# ES_Datalogger.net
KiCad netlist of a schematic drawn in EAGLE
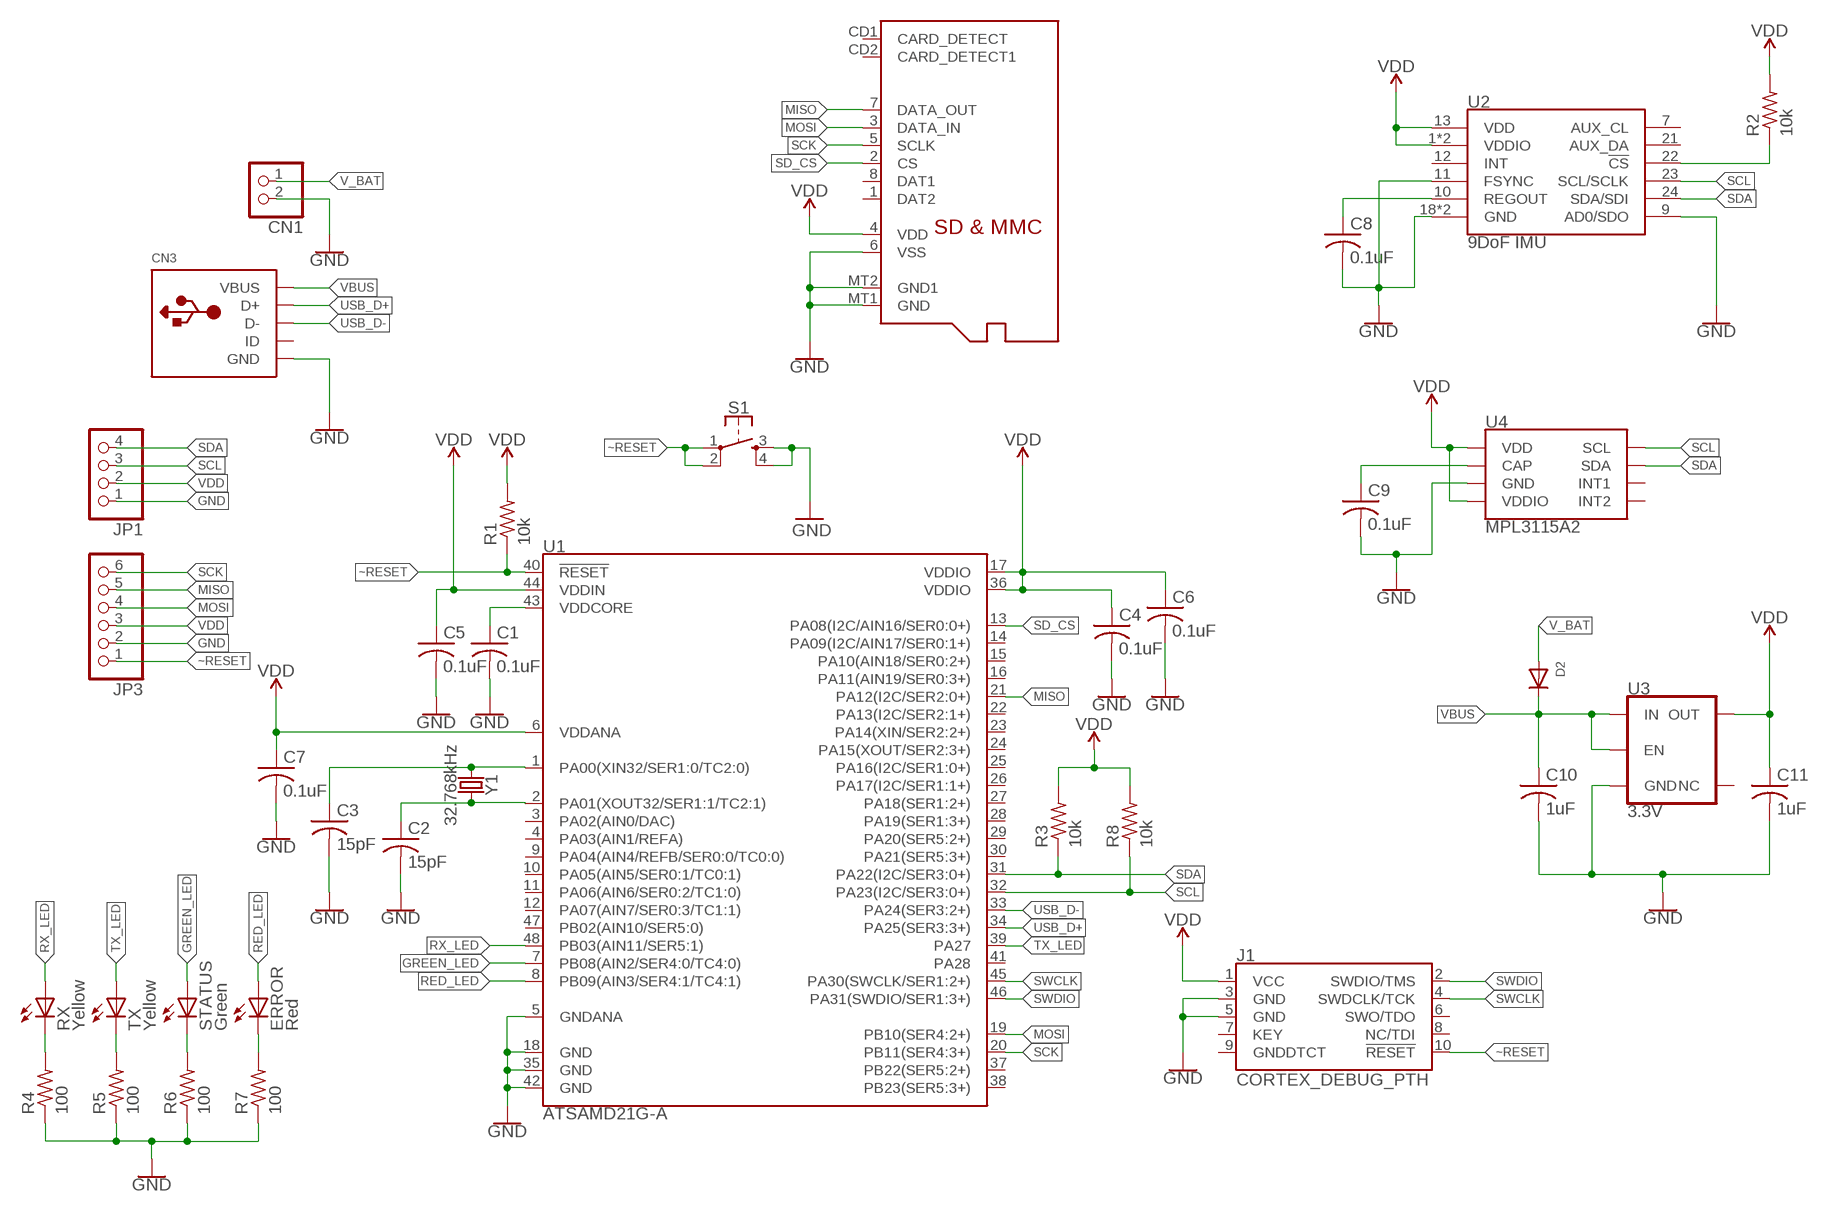
[diagram p0: schematic, sheet 1]

(export (version "E")
  (design (tool "Eeschema 10.0.6"))
  (components
    (comp (ref "C1")
      (value "0.1uF")
      (footprint "eagle-import:C0805")
      (libsource (lib "eagle-import") (part "C-USC0805"))
    )
    (comp (ref "C2")
      (value "15pF")
      (footprint "eagle-import:C0805")
      (libsource (lib "eagle-import") (part "C-USC0805"))
    )
    (comp (ref "C3")
      (value "15pF")
      (footprint "eagle-import:C0805")
      (libsource (lib "eagle-import") (part "C-USC0805"))
    )
    (comp (ref "C4")
      (value "0.1uF")
      (footprint "eagle-import:C0805")
      (libsource (lib "eagle-import") (part "C-USC0805"))
    )
    (comp (ref "C5")
      (value "0.1uF")
      (footprint "eagle-import:C0805")
      (libsource (lib "eagle-import") (part "C-USC0805"))
    )
    (comp (ref "C6")
      (value "0.1uF")
      (footprint "eagle-import:C0805")
      (libsource (lib "eagle-import") (part "C-USC0805"))
    )
    (comp (ref "C7")
      (value "0.1uF")
      (footprint "eagle-import:C0805")
      (libsource (lib "eagle-import") (part "C-USC0805"))
    )
    (comp (ref "C8")
      (value "0.1uF")
      (footprint "eagle-import:C0805")
      (libsource (lib "eagle-import") (part "C-USC0805"))
    )
    (comp (ref "C9")
      (value "0.1uF")
      (footprint "eagle-import:C0805")
      (libsource (lib "eagle-import") (part "C-USC0805"))
    )
    (comp (ref "C10")
      (value "1uF")
      (footprint "eagle-import:C0805")
      (libsource (lib "eagle-import") (part "C-USC0805"))
    )
    (comp (ref "C11")
      (value "1uF")
      (footprint "eagle-import:C0805")
      (libsource (lib "eagle-import") (part "C-USC0805"))
    )
    (comp (ref "CN1")
      (value "JST_2PIN-SMT")
      (footprint "eagle-import:JST-PH-2-SMT")
      (libsource (lib "eagle-import") (part "JST_2PIN-SMT"))
    )
    (comp (ref "CN3")
      (value "USBMOLEX")
      (footprint "eagle-import:USB-MINIB-THM-MOLEX")
      (libsource (lib "eagle-import") (part "USBMOLEX"))
    )
    (comp (ref "D2")
      (value "DIODE_SOD-123FL")
      (footprint "eagle-import:SOD-123FL")
      (libsource (lib "eagle-import") (part "DIODE_SOD-123FL"))
    )
    (comp (ref "ERROR")
      (value "Red")
      (footprint "eagle-import:CHIPLED_0805")
      (libsource (lib "eagle-import") (part "LEDCHIPLED_0805"))
    )
    (comp (ref "J1")
      (value "CORTEX_DEBUG_PTH")
      (footprint "eagle-import:2X5-PTH-1.27MM")
      (libsource (lib "eagle-import") (part "CORTEX_DEBUG_PTH"))
    )
    (comp (ref "JP1")
      (value "PINHD-1X4")
      (footprint "eagle-import:1X04")
      (libsource (lib "eagle-import") (part "PINHD-1X4"))
    )
    (comp (ref "JP3")
      (value "PINHD-1X6")
      (footprint "eagle-import:1X06")
      (libsource (lib "eagle-import") (part "PINHD-1X6"))
    )
    (comp (ref "R1")
      (value "10k")
      (footprint "eagle-import:R0805")
      (libsource (lib "eagle-import") (part "R-US_R0805"))
    )
    (comp (ref "R2")
      (value "10k")
      (footprint "eagle-import:R0805")
      (libsource (lib "eagle-import") (part "R-US_R0805"))
    )
    (comp (ref "R3")
      (value "10k")
      (footprint "eagle-import:R0805")
      (libsource (lib "eagle-import") (part "R-US_R0805"))
    )
    (comp (ref "R4")
      (value "100")
      (footprint "eagle-import:R0805")
      (libsource (lib "eagle-import") (part "R-US_R0805"))
    )
    (comp (ref "R5")
      (value "100")
      (footprint "eagle-import:R0805")
      (libsource (lib "eagle-import") (part "R-US_R0805"))
    )
    (comp (ref "R6")
      (value "100")
      (footprint "eagle-import:R0805")
      (libsource (lib "eagle-import") (part "R-US_R0805"))
    )
    (comp (ref "R7")
      (value "100")
      (footprint "eagle-import:R0805")
      (libsource (lib "eagle-import") (part "R-US_R0805"))
    )
    (comp (ref "R8")
      (value "10k")
      (footprint "eagle-import:R0805")
      (libsource (lib "eagle-import") (part "R-US_R0805"))
    )
    (comp (ref "RX")
      (value "Yellow")
      (footprint "eagle-import:CHIPLED_0805")
      (libsource (lib "eagle-import") (part "LEDCHIPLED_0805"))
    )
    (comp (ref "S1")
      (value "MOMENTARY-SWITCH-SPST-2-SMD-5.2MM")
      (footprint "eagle-import:TACTILE_SWITCH_SMD_5.2MM")
      (libsource (lib "eagle-import") (part "MOMENTARY-SWITCH-SPST-2-SMD-5.2MM"))
    )
    (comp (ref "STATUS")
      (value "Green")
      (footprint "eagle-import:CHIPLED_0805")
      (libsource (lib "eagle-import") (part "LEDCHIPLED_0805"))
    )
    (comp (ref "TX")
      (value "Yellow")
      (footprint "eagle-import:CHIPLED_0805")
      (libsource (lib "eagle-import") (part "LEDCHIPLED_0805"))
    )
    (comp (ref "U$1")
      (value "MICROSD")
      (footprint "eagle-import:MICROSD")
      (libsource (lib "eagle-import") (part "MICROSD"))
    )
    (comp (ref "U1")
      (value "ATSAMD21G-A")
      (footprint "eagle-import:TQFP-48")
      (libsource (lib "eagle-import") (part "ATSAMD21G-A"))
    )
    (comp (ref "U2")
      (value "9DoF IMU")
      (footprint "eagle-import:QFN24-3X3")
      (libsource (lib "eagle-import") (part "MPU-9250"))
    )
    (comp (ref "U3")
      (value "3.3V")
      (footprint "eagle-import:SOT23-5")
      (libsource (lib "eagle-import") (part "V_REG_AP2112K-3.3V"))
    )
    (comp (ref "U4")
      (value "MPL3115A2")
      (footprint "eagle-import:LGA-8-5X3")
      (libsource (lib "eagle-import") (part "MPL3115A2"))
    )
    (comp (ref "Y1")
      (value "32.768kHz")
      (footprint "eagle-import:CRYSTAL-SMD-MC-146")
      (libsource (lib "eagle-import") (part "CRYSTAL-32.768KHZSMD-MC146"))
    )
  )
  (nets
    (net (code "1") (name "/~{RESET}") (class "Default")
      (node (ref "J1") (pin "10") (pinfunction "~{RESET}_10") (pintype "bidirectional"))
      (node (ref "JP3") (pin "1") (pinfunction "1_1") (pintype "passive"))
      (node (ref "R1") (pin "1") (pinfunction "1_1") (pintype "passive"))
      (node (ref "S1") (pin "1") (pinfunction "1_1") (pintype "passive"))
      (node (ref "S1") (pin "2") (pinfunction "2_2") (pintype "passive"))
      (node (ref "U1") (pin "40") (pinfunction "~{RESET}_40") (pintype "bidirectional"))
    )
    (net (code "2") (name "GND") (class "Default")
      (node (ref "C1") (pin "2") (pinfunction "2_2") (pintype "passive"))
      (node (ref "C10") (pin "2") (pinfunction "2_2") (pintype "passive"))
      (node (ref "C11") (pin "2") (pinfunction "2_2") (pintype "passive"))
      (node (ref "C2") (pin "2") (pinfunction "2_2") (pintype "passive"))
      (node (ref "C3") (pin "2") (pinfunction "2_2") (pintype "passive"))
      (node (ref "C4") (pin "2") (pinfunction "2_2") (pintype "passive"))
      (node (ref "C5") (pin "2") (pinfunction "2_2") (pintype "passive"))
      (node (ref "C6") (pin "2") (pinfunction "2_2") (pintype "passive"))
      (node (ref "C7") (pin "2") (pinfunction "2_2") (pintype "passive"))
      (node (ref "C8") (pin "2") (pinfunction "2_2") (pintype "passive"))
      (node (ref "C9") (pin "2") (pinfunction "2_2") (pintype "passive"))
      (node (ref "CN1") (pin "2") (pinfunction "1_2") (pintype "passive"))
      (node (ref "CN3") (pin "GND") (pinfunction "GND_GND") (pintype "power_in"))
      (node (ref "J1") (pin "3") (pinfunction "GND_3") (pintype "bidirectional"))
      (node (ref "J1") (pin "5") (pinfunction "GND_5") (pintype "bidirectional"))
      (node (ref "JP1") (pin "1") (pinfunction "1_1") (pintype "passive"))
      (node (ref "JP3") (pin "2") (pinfunction "2_2") (pintype "passive"))
      (node (ref "R4") (pin "1") (pinfunction "1_1") (pintype "passive"))
      (node (ref "R5") (pin "1") (pinfunction "1_1") (pintype "passive"))
      (node (ref "R6") (pin "1") (pinfunction "1_1") (pintype "passive"))
      (node (ref "R7") (pin "1") (pinfunction "1_1") (pintype "passive"))
      (node (ref "S1") (pin "3") (pinfunction "3_3") (pintype "passive"))
      (node (ref "S1") (pin "4") (pinfunction "4_4") (pintype "passive"))
      (node (ref "U$1") (pin "6") (pinfunction "VSS_6") (pintype "power_in"))
      (node (ref "U$1") (pin "MT1") (pinfunction "GND_MT1") (pintype "power_in"))
      (node (ref "U$1") (pin "MT2") (pinfunction "GND1_MT2") (pintype "power_in"))
      (node (ref "U1") (pin "18") (pinfunction "GND_18") (pintype "bidirectional"))
      (node (ref "U1") (pin "35") (pinfunction "GND_35") (pintype "bidirectional"))
      (node (ref "U1") (pin "42") (pinfunction "GND_42") (pintype "bidirectional"))
      (node (ref "U1") (pin "5") (pinfunction "GNDANA_5") (pintype "bidirectional"))
      (node (ref "U2") (pin "11") (pinfunction "FSYNC_11") (pintype "bidirectional"))
      (node (ref "U2") (pin "18") (pinfunction "GND_18") (pintype "bidirectional"))
      (node (ref "U2") (pin "20") (pinfunction "GND_20") (pintype "bidirectional"))
      (node (ref "U2") (pin "9") (pinfunction "AD0/SDO_9") (pintype "bidirectional"))
      (node (ref "U3") (pin "2") (pinfunction "GND_2") (pintype "input"))
      (node (ref "U4") (pin "3") (pinfunction "GND_3") (pintype "power_in"))
    )
    (net (code "3") (name "GREEN_LED") (class "Default")
      (node (ref "STATUS") (pin "A") (pinfunction "A_A") (pintype "passive"))
      (node (ref "U1") (pin "7") (pinfunction "PB08(AIN2/SER4:0/TC4:0)_7") (pintype "bidirectional"))
    )
    (net (code "4") (name "MISO") (class "Default")
      (node (ref "JP3") (pin "5") (pinfunction "5_5") (pintype "passive"))
      (node (ref "U$1") (pin "7") (pinfunction "DATA_OUT_7") (pintype "output"))
      (node (ref "U1") (pin "21") (pinfunction "PA12(I2C/SER2:0+)_21") (pintype "bidirectional"))
    )
    (net (code "5") (name "MOSI") (class "Default")
      (node (ref "JP3") (pin "4") (pinfunction "4_4") (pintype "passive"))
      (node (ref "U$1") (pin "3") (pinfunction "DATA_IN_3") (pintype "input"))
      (node (ref "U1") (pin "19") (pinfunction "PB10(SER4:2+)_19") (pintype "bidirectional"))
    )
    (net (code "6") (name "Net-(ERROR-PadC)") (class "Default")
      (node (ref "ERROR") (pin "C") (pinfunction "C_C") (pintype "passive"))
      (node (ref "R7") (pin "2") (pinfunction "2_2") (pintype "passive"))
    )
    (net (code "7") (name "Net-(R4-Pad2)") (class "Default")
      (node (ref "R4") (pin "2") (pinfunction "2_2") (pintype "passive"))
      (node (ref "RX") (pin "C") (pinfunction "C_C") (pintype "passive"))
    )
    (net (code "8") (name "Net-(R5-Pad2)") (class "Default")
      (node (ref "R5") (pin "2") (pinfunction "2_2") (pintype "passive"))
      (node (ref "TX") (pin "C") (pinfunction "C_C") (pintype "passive"))
    )
    (net (code "9") (name "Net-(R6-Pad2)") (class "Default")
      (node (ref "R6") (pin "2") (pinfunction "2_2") (pintype "passive"))
      (node (ref "STATUS") (pin "C") (pinfunction "C_C") (pintype "passive"))
    )
    (net (code "10") (name "Net-(U1-PA00(XIN32{slash}SER1:0{slash}TC2:0))") (class "Default")
      (node (ref "C3") (pin "1") (pinfunction "1_1") (pintype "passive"))
      (node (ref "U1") (pin "1") (pinfunction "PA00(XIN32/SER1:0/TC2:0)_1") (pintype "bidirectional"))
      (node (ref "Y1") (pin "P$2") (pinfunction "1_P$2") (pintype "passive"))
    )
    (net (code "11") (name "Net-(U1-PA01(XOUT32{slash}SER1:1{slash}TC2:1))") (class "Default")
      (node (ref "C2") (pin "1") (pinfunction "1_1") (pintype "passive"))
      (node (ref "U1") (pin "2") (pinfunction "PA01(XOUT32/SER1:1/TC2:1)_2") (pintype "bidirectional"))
      (node (ref "Y1") (pin "P$1") (pinfunction "2_P$1") (pintype "passive"))
    )
    (net (code "12") (name "Net-(U1-VDDCORE)") (class "Default")
      (node (ref "C1") (pin "1") (pinfunction "1_1") (pintype "passive"))
      (node (ref "U1") (pin "43") (pinfunction "VDDCORE_43") (pintype "bidirectional"))
    )
    (net (code "13") (name "Net-(U2-REGOUT)") (class "Default")
      (node (ref "C8") (pin "1") (pinfunction "1_1") (pintype "passive"))
      (node (ref "U2") (pin "10") (pinfunction "REGOUT_10") (pintype "bidirectional"))
    )
    (net (code "14") (name "Net-(U2-~{CS})") (class "Default")
      (node (ref "R2") (pin "1") (pinfunction "1_1") (pintype "passive"))
      (node (ref "U2") (pin "22") (pinfunction "~{CS}_22") (pintype "bidirectional"))
    )
    (net (code "15") (name "Net-(U4-CAP)") (class "Default")
      (node (ref "C9") (pin "1") (pinfunction "1_1") (pintype "passive"))
      (node (ref "U4") (pin "2") (pinfunction "CAP_2") (pintype "power_in"))
    )
    (net (code "16") (name "RED_LED") (class "Default")
      (node (ref "ERROR") (pin "A") (pinfunction "A_A") (pintype "passive"))
      (node (ref "U1") (pin "8") (pinfunction "PB09(AIN3/SER4:1/TC4:1)_8") (pintype "bidirectional"))
    )
    (net (code "17") (name "RX_LED") (class "Default")
      (node (ref "RX") (pin "A") (pinfunction "A_A") (pintype "passive"))
      (node (ref "U1") (pin "48") (pinfunction "PB03(AIN11/SER5:1)_48") (pintype "bidirectional"))
    )
    (net (code "18") (name "SCK") (class "Default")
      (node (ref "JP3") (pin "6") (pinfunction "6_6") (pintype "passive"))
      (node (ref "U$1") (pin "5") (pinfunction "SCLK_5") (pintype "input"))
      (node (ref "U1") (pin "20") (pinfunction "PB11(SER4:3+)_20") (pintype "bidirectional"))
    )
    (net (code "19") (name "SCL") (class "Default")
      (node (ref "JP1") (pin "3") (pinfunction "3_3") (pintype "passive"))
      (node (ref "R8") (pin "1") (pinfunction "1_1") (pintype "passive"))
      (node (ref "U1") (pin "32") (pinfunction "PA23(I2C/SER3:0+)_32") (pintype "bidirectional"))
      (node (ref "U2") (pin "23") (pinfunction "SCL/SCLK_23") (pintype "bidirectional"))
      (node (ref "U4") (pin "8") (pinfunction "SCL_8") (pintype "bidirectional"))
    )
    (net (code "20") (name "SDA") (class "Default")
      (node (ref "JP1") (pin "4") (pinfunction "4_4") (pintype "passive"))
      (node (ref "R3") (pin "1") (pinfunction "1_1") (pintype "passive"))
      (node (ref "U1") (pin "31") (pinfunction "PA22(I2C/SER3:0+)_31") (pintype "bidirectional"))
      (node (ref "U2") (pin "24") (pinfunction "SDA/SDI_24") (pintype "bidirectional"))
      (node (ref "U4") (pin "7") (pinfunction "SDA_7") (pintype "bidirectional"))
    )
    (net (code "21") (name "SD_CS") (class "Default")
      (node (ref "U$1") (pin "2") (pinfunction "CS_2") (pintype "input"))
      (node (ref "U1") (pin "13") (pinfunction "PA08(I2C/AIN16/SER0:0+)_13") (pintype "bidirectional"))
    )
    (net (code "22") (name "SWCLK") (class "Default")
      (node (ref "J1") (pin "4") (pinfunction "SWDCLK/TCK_4") (pintype "bidirectional"))
      (node (ref "U1") (pin "45") (pinfunction "PA30(SWCLK/SER1:2+)_45") (pintype "bidirectional"))
    )
    (net (code "23") (name "SWDIO") (class "Default")
      (node (ref "J1") (pin "2") (pinfunction "SWDIO/TMS_2") (pintype "bidirectional"))
      (node (ref "U1") (pin "46") (pinfunction "PA31(SWDIO/SER1:3+)_46") (pintype "bidirectional"))
    )
    (net (code "24") (name "TX_LED") (class "Default")
      (node (ref "TX") (pin "A") (pinfunction "A_A") (pintype "passive"))
      (node (ref "U1") (pin "39") (pinfunction "PA27_39") (pintype "bidirectional"))
    )
    (net (code "25") (name "USB_D+") (class "Default")
      (node (ref "CN3") (pin "D+") (pinfunction "D+_D+") (pintype "bidirectional"))
      (node (ref "U1") (pin "34") (pinfunction "PA25(SER3:3+)_34") (pintype "bidirectional"))
    )
    (net (code "26") (name "USB_D-") (class "Default")
      (node (ref "CN3") (pin "D-") (pinfunction "D-_D-") (pintype "bidirectional"))
      (node (ref "U1") (pin "33") (pinfunction "PA24(SER3:2+)_33") (pintype "bidirectional"))
    )
    (net (code "27") (name "VBUS") (class "Default")
      (node (ref "C10") (pin "1") (pinfunction "1_1") (pintype "passive"))
      (node (ref "CN3") (pin "VBUS") (pinfunction "VBUS_VBUS") (pintype "power_in"))
      (node (ref "D2") (pin "C") (pinfunction "C_C") (pintype "passive"))
      (node (ref "U3") (pin "1") (pinfunction "IN_1") (pintype "input"))
      (node (ref "U3") (pin "3") (pinfunction "EN_3") (pintype "input"))
    )
    (net (code "28") (name "VDD") (class "Default")
      (node (ref "C11") (pin "1") (pinfunction "1_1") (pintype "passive"))
      (node (ref "C4") (pin "1") (pinfunction "1_1") (pintype "passive"))
      (node (ref "C5") (pin "1") (pinfunction "1_1") (pintype "passive"))
      (node (ref "C6") (pin "1") (pinfunction "1_1") (pintype "passive"))
      (node (ref "C7") (pin "1") (pinfunction "1_1") (pintype "passive"))
      (node (ref "J1") (pin "1") (pinfunction "VCC_1") (pintype "bidirectional"))
      (node (ref "JP1") (pin "2") (pinfunction "2_2") (pintype "passive"))
      (node (ref "JP3") (pin "3") (pinfunction "3_3") (pintype "passive"))
      (node (ref "R1") (pin "2") (pinfunction "2_2") (pintype "passive"))
      (node (ref "R2") (pin "2") (pinfunction "2_2") (pintype "passive"))
      (node (ref "R3") (pin "2") (pinfunction "2_2") (pintype "passive"))
      (node (ref "R8") (pin "2") (pinfunction "2_2") (pintype "passive"))
      (node (ref "U$1") (pin "4") (pinfunction "VDD_4") (pintype "power_in"))
      (node (ref "U1") (pin "17") (pinfunction "VDDIO_17") (pintype "bidirectional"))
      (node (ref "U1") (pin "36") (pinfunction "VDDIO_36") (pintype "bidirectional"))
      (node (ref "U1") (pin "44") (pinfunction "VDDIN_44") (pintype "bidirectional"))
      (node (ref "U1") (pin "6") (pinfunction "VDDANA_6") (pintype "bidirectional"))
      (node (ref "U2") (pin "1") (pinfunction "VDDIO_1") (pintype "bidirectional"))
      (node (ref "U2") (pin "13") (pinfunction "VDD_13") (pintype "bidirectional"))
      (node (ref "U2") (pin "8") (pinfunction "VDDIO_8") (pintype "bidirectional"))
      (node (ref "U3") (pin "5") (pinfunction "OUT_5") (pintype "passive"))
      (node (ref "U4") (pin "1") (pinfunction "VDD_1") (pintype "power_in"))
      (node (ref "U4") (pin "4") (pinfunction "VDDIO_4") (pintype "power_in"))
    )
    (net (code "29") (name "V_BAT") (class "Default")
      (node (ref "CN1") (pin "1") (pinfunction "2_1") (pintype "passive"))
      (node (ref "D2") (pin "A") (pinfunction "A_A") (pintype "passive"))
    )
    (net (code "30") (name "unconnected-(CN3-PadID)") (class "Default")
      (node (ref "CN3") (pin "ID") (pinfunction "ID_ID") (pintype "bidirectional"))
    )
    (net (code "31") (name "unconnected-(J1-GNDDTCT-Pad9)") (class "Default")
      (node (ref "J1") (pin "9") (pinfunction "GNDDTCT_9") (pintype "bidirectional"))
    )
    (net (code "32") (name "unconnected-(J1-KEY-Pad7)") (class "Default")
      (node (ref "J1") (pin "7") (pinfunction "KEY_7") (pintype "bidirectional"))
    )
    (net (code "33") (name "unconnected-(J1-NC{slash}TDI-Pad8)") (class "Default")
      (node (ref "J1") (pin "8") (pinfunction "NC/TDI_8") (pintype "bidirectional"))
    )
    (net (code "34") (name "unconnected-(J1-SWO{slash}TDO-Pad6)") (class "Default")
      (node (ref "J1") (pin "6") (pinfunction "SWO/TDO_6") (pintype "bidirectional"))
    )
    (net (code "35") (name "unconnected-(U$1-CARD_DETECT-PadCD1)") (class "Default")
      (node (ref "U$1") (pin "CD1") (pinfunction "CARD_DETECT_CD1") (pintype "passive"))
    )
    (net (code "36") (name "unconnected-(U$1-CARD_DETECT1-PadCD2)") (class "Default")
      (node (ref "U$1") (pin "CD2") (pinfunction "CARD_DETECT1_CD2") (pintype "passive"))
    )
    (net (code "37") (name "unconnected-(U$1-DAT1-Pad8)") (class "Default")
      (node (ref "U$1") (pin "8") (pinfunction "DAT1_8") (pintype "bidirectional"))
    )
    (net (code "38") (name "unconnected-(U$1-DAT2-Pad1)") (class "Default")
      (node (ref "U$1") (pin "1") (pinfunction "DAT2_1") (pintype "bidirectional"))
    )
    (net (code "39") (name "unconnected-(U1-PA02(AIN0{slash}DAC)-Pad3)") (class "Default")
      (node (ref "U1") (pin "3") (pinfunction "PA02(AIN0/DAC)_3") (pintype "bidirectional"))
    )
    (net (code "40") (name "unconnected-(U1-PA03(AIN1{slash}REFA)-Pad4)") (class "Default")
      (node (ref "U1") (pin "4") (pinfunction "PA03(AIN1/REFA)_4") (pintype "bidirectional"))
    )
    (net (code "41") (name "unconnected-(U1-PA04(AIN4{slash}REFB{slash}SER0:0{slash}TC0:0)-Pad9)") (class "Default")
      (node (ref "U1") (pin "9") (pinfunction "PA04(AIN4/REFB/SER0:0/TC0:0)_9") (pintype "bidirectional"))
    )
    (net (code "42") (name "unconnected-(U1-PA05(AIN5{slash}SER0:1{slash}TC0:1)-Pad10)") (class "Default")
      (node (ref "U1") (pin "10") (pinfunction "PA05(AIN5/SER0:1/TC0:1)_10") (pintype "bidirectional"))
    )
    (net (code "43") (name "unconnected-(U1-PA06(AIN6{slash}SER0:2{slash}TC1:0)-Pad11)") (class "Default")
      (node (ref "U1") (pin "11") (pinfunction "PA06(AIN6/SER0:2/TC1:0)_11") (pintype "bidirectional"))
    )
    (net (code "44") (name "unconnected-(U1-PA07(AIN7{slash}SER0:3{slash}TC1:1)-Pad12)") (class "Default")
      (node (ref "U1") (pin "12") (pinfunction "PA07(AIN7/SER0:3/TC1:1)_12") (pintype "bidirectional"))
    )
    (net (code "45") (name "unconnected-(U1-PA09(I2C{slash}AIN17{slash}SER0:1+)-Pad14)") (class "Default")
      (node (ref "U1") (pin "14") (pinfunction "PA09(I2C/AIN17/SER0:1+)_14") (pintype "bidirectional"))
    )
    (net (code "46") (name "unconnected-(U1-PA10(AIN18{slash}SER0:2+)-Pad15)") (class "Default")
      (node (ref "U1") (pin "15") (pinfunction "PA10(AIN18/SER0:2+)_15") (pintype "bidirectional"))
    )
    (net (code "47") (name "unconnected-(U1-PA11(AIN19{slash}SER0:3+)-Pad16)") (class "Default")
      (node (ref "U1") (pin "16") (pinfunction "PA11(AIN19/SER0:3+)_16") (pintype "bidirectional"))
    )
    (net (code "48") (name "unconnected-(U1-PA13(I2C{slash}SER2:1+)-Pad22)") (class "Default")
      (node (ref "U1") (pin "22") (pinfunction "PA13(I2C/SER2:1+)_22") (pintype "bidirectional"))
    )
    (net (code "49") (name "unconnected-(U1-PA14(XIN{slash}SER2:2+)-Pad23)") (class "Default")
      (node (ref "U1") (pin "23") (pinfunction "PA14(XIN/SER2:2+)_23") (pintype "bidirectional"))
    )
    (net (code "50") (name "unconnected-(U1-PA15(XOUT{slash}SER2:3+)-Pad24)") (class "Default")
      (node (ref "U1") (pin "24") (pinfunction "PA15(XOUT/SER2:3+)_24") (pintype "bidirectional"))
    )
    (net (code "51") (name "unconnected-(U1-PA16(I2C{slash}SER1:0+)-Pad25)") (class "Default")
      (node (ref "U1") (pin "25") (pinfunction "PA16(I2C/SER1:0+)_25") (pintype "bidirectional"))
    )
    (net (code "52") (name "unconnected-(U1-PA17(I2C{slash}SER1:1+)-Pad26)") (class "Default")
      (node (ref "U1") (pin "26") (pinfunction "PA17(I2C/SER1:1+)_26") (pintype "bidirectional"))
    )
    (net (code "53") (name "unconnected-(U1-PA18(SER1:2+)-Pad27)") (class "Default")
      (node (ref "U1") (pin "27") (pinfunction "PA18(SER1:2+)_27") (pintype "bidirectional"))
    )
    (net (code "54") (name "unconnected-(U1-PA19(SER1:3+)-Pad28)") (class "Default")
      (node (ref "U1") (pin "28") (pinfunction "PA19(SER1:3+)_28") (pintype "bidirectional"))
    )
    (net (code "55") (name "unconnected-(U1-PA20(SER5:2+)-Pad29)") (class "Default")
      (node (ref "U1") (pin "29") (pinfunction "PA20(SER5:2+)_29") (pintype "bidirectional"))
    )
    (net (code "56") (name "unconnected-(U1-PA21(SER5:3+)-Pad30)") (class "Default")
      (node (ref "U1") (pin "30") (pinfunction "PA21(SER5:3+)_30") (pintype "bidirectional"))
    )
    (net (code "57") (name "unconnected-(U1-PA28-Pad41)") (class "Default")
      (node (ref "U1") (pin "41") (pinfunction "PA28_41") (pintype "bidirectional"))
    )
    (net (code "58") (name "unconnected-(U1-PB02(AIN10{slash}SER5:0)-Pad47)") (class "Default")
      (node (ref "U1") (pin "47") (pinfunction "PB02(AIN10/SER5:0)_47") (pintype "bidirectional"))
    )
    (net (code "59") (name "unconnected-(U1-PB22(SER5:2+)-Pad37)") (class "Default")
      (node (ref "U1") (pin "37") (pinfunction "PB22(SER5:2+)_37") (pintype "bidirectional"))
    )
    (net (code "60") (name "unconnected-(U1-PB23(SER5:3+)-Pad38)") (class "Default")
      (node (ref "U1") (pin "38") (pinfunction "PB23(SER5:3+)_38") (pintype "bidirectional"))
    )
    (net (code "61") (name "unconnected-(U2-AUX_CL-Pad7)") (class "Default")
      (node (ref "U2") (pin "7") (pinfunction "AUX_CL_7") (pintype "bidirectional"))
    )
    (net (code "62") (name "unconnected-(U2-AUX_DA-Pad21)") (class "Default")
      (node (ref "U2") (pin "21") (pinfunction "AUX_DA_21") (pintype "bidirectional"))
    )
    (net (code "63") (name "unconnected-(U2-INT-Pad12)") (class "Default")
      (node (ref "U2") (pin "12") (pinfunction "INT_12") (pintype "bidirectional"))
    )
    (net (code "64") (name "unconnected-(U3-NC-Pad4)") (class "Default")
      (node (ref "U3") (pin "4") (pinfunction "NC_4") (pintype "no_connect"))
    )
    (net (code "65") (name "unconnected-(U4-INT1-Pad6)") (class "Default")
      (node (ref "U4") (pin "6") (pinfunction "INT1_6") (pintype "output"))
    )
    (net (code "66") (name "unconnected-(U4-INT2-Pad5)") (class "Default")
      (node (ref "U4") (pin "5") (pinfunction "INT2_5") (pintype "output"))
    )
  )
)
